# Microcontroller.net
KiCad netlist of a schematic drawn in Altium Designer
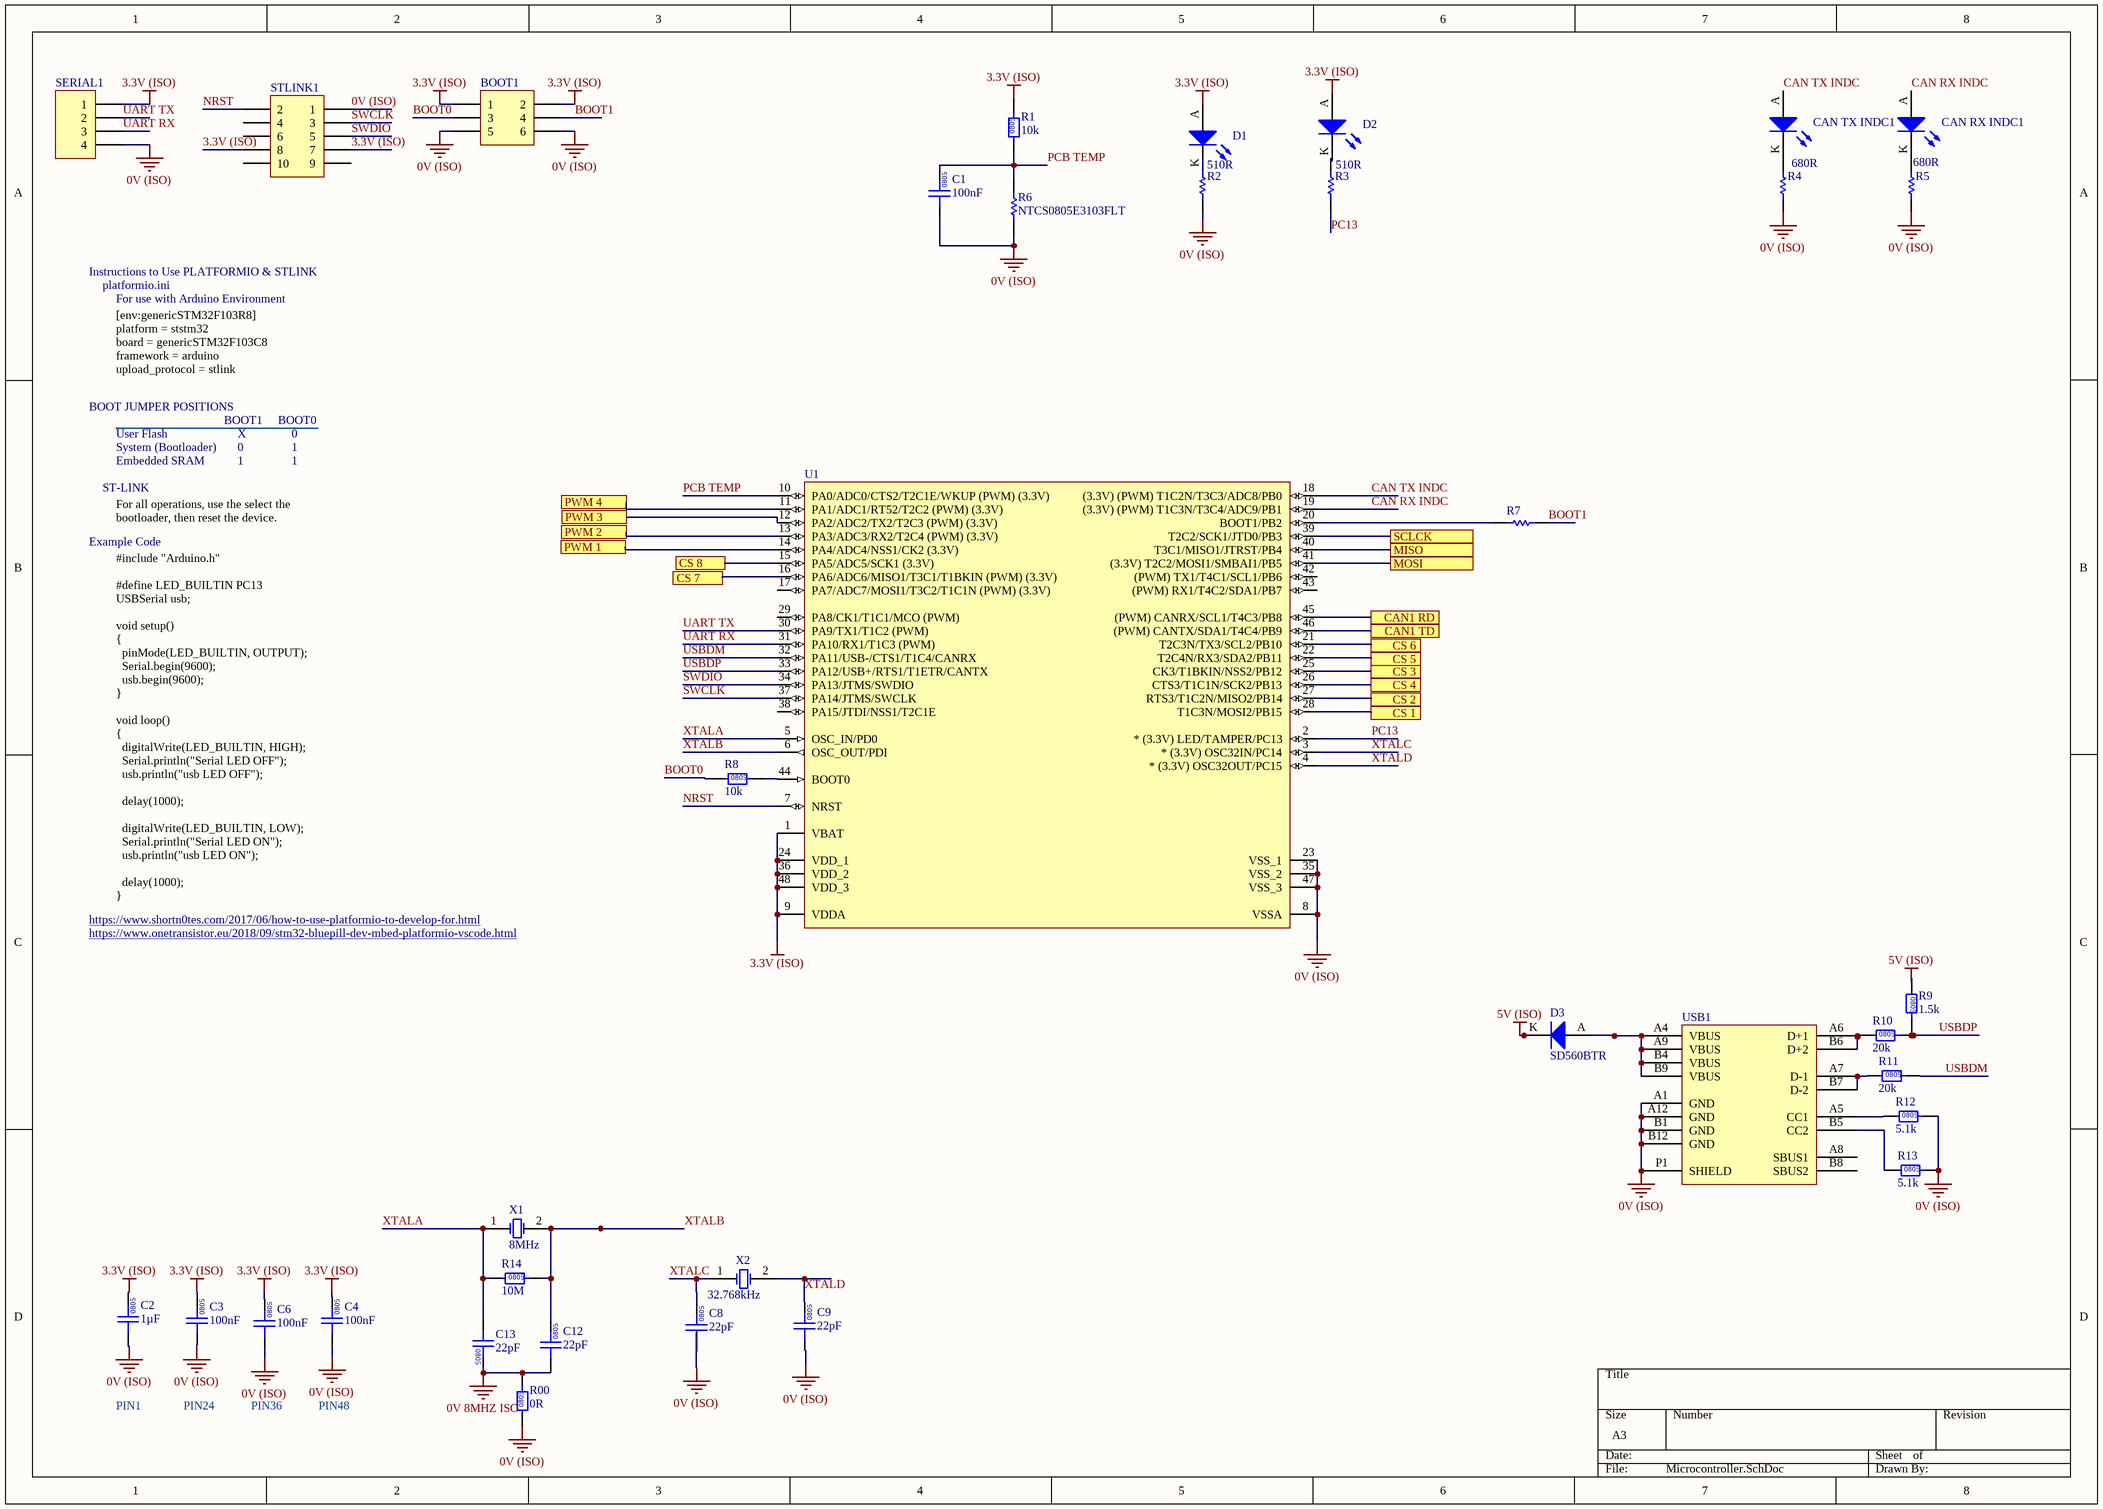
[diagram p0: Microcontroller.SchDoc]

(export (version "E")
  (design (tool "Eeschema 10.0.6"))
  (components
    (comp (ref "BOOT1")
      (value "~")
      (footprint "TH 2.54mm Header 2x3")
      (fields (field (name "PART NUMBER") "TH 2.54mm Header 2x3") (field (name "CONTACT") "NA"))
      (libsource (lib "ts_standard_connectors") (part "Header 2x3"))
    )
    (comp (ref "C1")
      (value "100nF")
      (footprint "0805")
      (fields
        (field (name "PART NUMBER") "GCM21BR71H104KA37L")
        (field (name "MANUFACTURER") "muRata")
        (field (name "TOLERANCE") "±10%")
      )
      (libsource (lib "ts_standard_library") (part "Capacitor 0805"))
    )
    (comp (ref "C2")
      (value "1µF")
      (footprint "0805")
      (fields
        (field (name "PART NUMBER") "GCM21BR71H105KA03L")
        (field (name "MANUFACTURER") "muRata")
        (field (name "TOLERANCE") "±10%")
      )
      (libsource (lib "ts_standard_library") (part "Capacitor 0805"))
    )
    (comp (ref "C3")
      (value "100nF")
      (footprint "0805")
      (fields
        (field (name "PART NUMBER") "GCM21BR71H104KA37L")
        (field (name "MANUFACTURER") "muRata")
        (field (name "TOLERANCE") "±10%")
      )
      (libsource (lib "ts_standard_library") (part "Capacitor 0805"))
    )
    (comp (ref "C4")
      (value "100nF")
      (footprint "0805")
      (fields
        (field (name "PART NUMBER") "GCM21BR71H104KA37L")
        (field (name "MANUFACTURER") "muRata")
        (field (name "TOLERANCE") "±10%")
      )
      (libsource (lib "ts_standard_library") (part "Capacitor 0805"))
    )
    (comp (ref "C6")
      (value "100nF")
      (footprint "0805")
      (fields
        (field (name "PART NUMBER") "GCM21BR71H104KA37L")
        (field (name "MANUFACTURER") "muRata")
        (field (name "TOLERANCE") "±10%")
      )
      (libsource (lib "ts_standard_library") (part "Capacitor 0805"))
    )
    (comp (ref "C8")
      (value "22pF")
      (footprint "0805")
      (fields
        (field (name "PART NUMBER") "GRM21A5C2E220JW01D")
        (field (name "MANUFACTURER") "muRata")
        (field (name "TOLERANCE") "±5%")
      )
      (libsource (lib "ts_standard_library") (part "Capacitor 0805"))
    )
    (comp (ref "C9")
      (value "22pF")
      (footprint "0805")
      (fields
        (field (name "PART NUMBER") "GRM21A5C2E220JW01D")
        (field (name "MANUFACTURER") "muRata")
        (field (name "TOLERANCE") "±5%")
      )
      (libsource (lib "ts_standard_library") (part "Capacitor 0805"))
    )
    (comp (ref "C12")
      (value "22pF")
      (footprint "0805")
      (fields
        (field (name "PART NUMBER") "GRM21A5C2E220JW01D")
        (field (name "MANUFACTURER") "muRata")
        (field (name "TOLERANCE") "±5%")
      )
      (libsource (lib "ts_standard_library") (part "Capacitor 0805"))
    )
    (comp (ref "C13")
      (value "22pF")
      (footprint "0805")
      (fields
        (field (name "PART NUMBER") "GRM21A5C2E220JW01D")
        (field (name "MANUFACTURER") "muRata")
        (field (name "TOLERANCE") "±5%")
      )
      (libsource (lib "ts_standard_library") (part "Capacitor 0805"))
    )
    (comp (ref "CAN RX INDC1")
      (value "~")
      (footprint "0805 LED")
      (description "LED BLUE CLEAR 2012 SMD")
      (fields
        (field (name "PART NUMBER") "SML-MN2BCTT86C")
        (field (name "MANUFACTURER") "ROHM Semiconductor")
      )
      (libsource (lib "ts_standard_library") (part "LED"))
    )
    (comp (ref "CAN TX INDC1")
      (value "~")
      (footprint "0805 LED")
      (description "LED BLUE CLEAR 2012 SMD")
      (fields
        (field (name "PART NUMBER") "SML-MN2BCTT86C")
        (field (name "MANUFACTURER") "ROHM Semiconductor")
      )
      (libsource (lib "ts_standard_library") (part "LED"))
    )
    (comp (ref "D1")
      (value "~")
      (footprint "0805 LED")
      (description "Red LED Indication - Discrete 1.75V 0805 (2012 Metric)")
      (fields (field (name "MANUFACTURER") "ROHM Semiconductor") (field (name "PART NUMBER") "SML-210LTT86"))
      (libsource (lib "ts_standard_library") (part "LED"))
    )
    (comp (ref "D2")
      (value "~")
      (footprint "0805 LED")
      (description "Red LED Indication - Discrete 1.75V 0805 (2012 Metric)")
      (fields (field (name "MANUFACTURER") "ROHM Semiconductor") (field (name "PART NUMBER") "SML-210LTT86"))
      (libsource (lib "ts_standard_library") (part "LED"))
    )
    (comp (ref "D3")
      (value "SD560BTR")
      (footprint "SMB Diode")
      (fields
        (field (name "MANUFACTURER") "SMC Diode Solutions")
        (field (name "DIGIKEY PART NUMBER") "1655-1530-2-ND")
      )
      (libsource (lib "ts_standard_library") (part "Diode"))
    )
    (comp (ref "R00")
      (value "0R")
      (footprint "0805")
      (fields
        (field (name "PART NUMBER") "RC0805FR070RL")
        (field (name "MANUFACTURER") "YAGEO")
        (field (name "TOLERANCE") "0.01")
      )
      (libsource (lib "ts_standard_library") (part "Resistor 0805"))
    )
    (comp (ref "R1")
      (value "10k")
      (footprint "0805")
      (fields
        (field (name "PART NUMBER") "RC0805FR0710KL")
        (field (name "MANUFACTURER") "YAGEO")
        (field (name "TOLERANCE") "0.01")
      )
      (libsource (lib "ts_standard_library") (part "Resistor 0805"))
    )
    (comp (ref "R2")
      (value "510R")
      (footprint "0805")
      (fields
        (field (name "MANUFACTURER") "YAGEO")
        (field (name "PART NUMBER") "RC0805FR07510RL")
        (field (name "TOLERANCE") "0.01")
      )
      (libsource (lib "ts_standard_library") (part "Resistor"))
    )
    (comp (ref "R3")
      (value "510R")
      (footprint "0805")
      (fields
        (field (name "MANUFACTURER") "YAGEO")
        (field (name "PART NUMBER") "RC0805FR07510RL")
        (field (name "TOLERANCE") "0.01")
      )
      (libsource (lib "ts_standard_library") (part "Resistor"))
    )
    (comp (ref "R4")
      (value "680R")
      (footprint "0805")
      (fields
        (field (name "PART NUMBER") "RC0805FR07680RL")
        (field (name "MANUFACTURER") "YAGEO")
        (field (name "TOLERANCE") "0.01")
      )
      (libsource (lib "ts_standard_library") (part "Resistor"))
    )
    (comp (ref "R5")
      (value "680R")
      (footprint "0805")
      (fields
        (field (name "PART NUMBER") "RC0805FR07680RL")
        (field (name "MANUFACTURER") "YAGEO")
        (field (name "TOLERANCE") "0.01")
      )
      (libsource (lib "ts_standard_library") (part "Resistor"))
    )
    (comp (ref "R6")
      (value "NTCS0805E3103FLT")
      (footprint "0805")
      (fields (field (name "TOLERANCE") "0.01") (field (name "DIGIKEY PART NUMBER") "BC2733CT-ND"))
      (libsource (lib "Team Swinburne") (part "Resistor"))
    )
    (comp (ref "R7")
      (value "~")
      (footprint "0805")
      (fields
        (field (name "PART NUMBER") "RC0805FR0710KL")
        (field (name "MANUFACTURER") "YAGEO")
        (field (name "TOLERANCE") "0.01")
      )
      (libsource (lib "ts_standard_library") (part "Resistor"))
    )
    (comp (ref "R8")
      (value "10k")
      (footprint "0805")
      (fields
        (field (name "PART NUMBER") "RC0805FR0710KL")
        (field (name "MANUFACTURER") "YAGEO")
        (field (name "TOLERANCE") "0.01")
      )
      (libsource (lib "ts_standard_library") (part "Resistor 0805"))
    )
    (comp (ref "R9")
      (value "1.5k")
      (footprint "0805")
      (fields
        (field (name "PART NUMBER") "RC0805FR071K5L")
        (field (name "MANUFACTURER") "YAGEO")
        (field (name "TOLERANCE") "0.01")
      )
      (libsource (lib "ts_standard_library") (part "Resistor 0805"))
    )
    (comp (ref "R10")
      (value "20k")
      (footprint "0805")
      (fields
        (field (name "PART NUMBER") "RC0805FR0720KL")
        (field (name "MANUFACTURER") "YAGEO")
        (field (name "TOLERANCE") "0.01")
      )
      (libsource (lib "ts_standard_library") (part "Resistor 0805"))
    )
    (comp (ref "R11")
      (value "20k")
      (footprint "0805")
      (fields
        (field (name "PART NUMBER") "RC0805FR0720KL")
        (field (name "MANUFACTURER") "YAGEO")
        (field (name "TOLERANCE") "0.01")
      )
      (libsource (lib "ts_standard_library") (part "Resistor 0805"))
    )
    (comp (ref "R12")
      (value "5.1k")
      (footprint "0805")
      (fields
        (field (name "PART NUMBER") "RC0805FR075K1L")
        (field (name "MANUFACTURER") "YAGEO")
        (field (name "TOLERANCE") "0.01")
      )
      (libsource (lib "ts_standard_library") (part "Resistor 0805"))
    )
    (comp (ref "R13")
      (value "5.1k")
      (footprint "0805")
      (fields
        (field (name "PART NUMBER") "RC0805FR075K1L")
        (field (name "MANUFACTURER") "YAGEO")
        (field (name "TOLERANCE") "0.01")
      )
      (libsource (lib "ts_standard_library") (part "Resistor 0805"))
    )
    (comp (ref "R14")
      (value "10M")
      (footprint "0805")
      (fields
        (field (name "PART NUMBER") "RC0805FR0710ML")
        (field (name "MANUFACTURER") "YAGEO")
        (field (name "TOLERANCE") "0.01")
      )
      (libsource (lib "ts_standard_library") (part "Resistor 0805"))
    )
    (comp (ref "SERIAL1")
      (value "~")
      (footprint "TH 2.54mm Header 1x4")
      (fields (field (name "PART NUMBER") "TH 2.54mm Header 1x4") (field (name "CONTACT") "NA"))
      (libsource (lib "ts_standard_connectors") (part "Header 1x4"))
    )
    (comp (ref "STLINK1")
      (value "~")
      (footprint "TH 2.54mm Header 2x5")
      (fields (field (name "PART NUMBER") "TH 2.54mm Header 2x5") (field (name "CONTACT") "NA"))
      (libsource (lib "ts_standard_connectors") (part "Header 2x5"))
    )
    (comp (ref "U1")
      (value "~")
      (footprint "STM 48-LQFP")
      (description "ARM® Cortex®-M3 STM32F1 Microcontroller IC 32-Bit 72MHz 64KB (64K x 8) FLASH")
      (fields (field (name "PART NUMBER") "STM32F103C8T6") (field (name "MANUFACTURER") "STMicroelectronics"))
      (libsource (lib "ts_standard_library") (part "STM32F103C8T6"))
    )
    (comp (ref "USB1")
      (value "~")
      (footprint "USB4085-GF-A")
      (description "USB - C (Type - C) USB 2.0 Receptacle Connector 16 Position Through Hole, Right Angle")
      (fields
        (field (name "PART NUMBER") "USB4085-GF-A")
        (field (name "DIGIKEY PART NUMBER") "2073-USB4085-GF-ACT-ND")
      )
      (libsource (lib "ts_standard_connectors") (part "USB4085-GF-A"))
    )
    (comp (ref "X1")
      (value "8MHz")
      (footprint "Abracon HC-49/US")
      (fields
        (field (name "PART NUMBER") "ABLS-8.000MHZ-B4-T")
        (field (name "MANUFACTURER") "Abracon LLC")
        (field (name "DIGIKEY PART NUMBER") "535-10212-2-ND")
      )
      (libsource (lib "ts_standard_library") (part "Crystal"))
    )
    (comp (ref "X2")
      (value "32.768kHz")
      (footprint "EPSON 2-SMD")
      (fields
        (field (name "PART NUMBER") "FC-135 32.7680KA-A5")
        (field (name "MANUFACTURER") "EPSON")
        (field (name "DIGIKEY PART NUMBER") "SER4103TR-ND")
      )
      (libsource (lib "ts_standard_library") (part "Crystal"))
    )
  )
  (nets
    (net (code "1") (name "/BOOT0") (class "Default")
      (node (ref "BOOT1") (pin "3") (pinfunction "3_3") (pintype "passive"))
      (node (ref "R8") (pin "1") (pinfunction "1_1") (pintype "passive"))
    )
    (net (code "2") (name "/BOOT1") (class "Default")
      (node (ref "BOOT1") (pin "4") (pinfunction "4_4") (pintype "passive"))
      (node (ref "R7") (pin "2") (pinfunction "2_2") (pintype "passive"))
    )
    (net (code "3") (name "/CAN RX INDC") (class "Default")
      (node (ref "CAN RX INDC1") (pin "A") (pinfunction "A_A") (pintype "passive"))
      (node (ref "U1") (pin "19") (pinfunction "(3.3V)_(PWM)_T1C3N/T3C4/ADC9/PB1_19") (pintype "bidirectional"))
    )
    (net (code "4") (name "/CAN TX INDC") (class "Default")
      (node (ref "CAN TX INDC1") (pin "A") (pinfunction "A_A") (pintype "passive"))
      (node (ref "U1") (pin "18") (pinfunction "(3.3V)_(PWM)_T1C2N/T3C3/ADC8/PB0_18") (pintype "bidirectional"))
    )
    (net (code "5") (name "/CAN1 RD") (class "Default")
      (node (ref "U1") (pin "45") (pinfunction "(PWM)_CANRX/SCL1/T4C3/PB8_45") (pintype "bidirectional"))
    )
    (net (code "6") (name "/CAN1 TD") (class "Default")
      (node (ref "U1") (pin "46") (pinfunction "(PWM)_CANTX/SDA1/T4C4/PB9_46") (pintype "bidirectional"))
    )
    (net (code "7") (name "/CS 1") (class "Default")
      (node (ref "U1") (pin "28") (pinfunction "T1C3N/MOSI2/PB15_28") (pintype "bidirectional"))
    )
    (net (code "8") (name "/CS 2") (class "Default")
      (node (ref "U1") (pin "27") (pinfunction "RTS3/T1C2N/MISO2/PB14_27") (pintype "bidirectional"))
    )
    (net (code "9") (name "/CS 3") (class "Default")
      (node (ref "U1") (pin "25") (pinfunction "CK3/T1BKIN/NSS2/PB12_25") (pintype "bidirectional"))
    )
    (net (code "10") (name "/CS 4") (class "Default")
      (node (ref "U1") (pin "26") (pinfunction "CTS3/T1C1N/SCK2/PB13_26") (pintype "bidirectional"))
    )
    (net (code "11") (name "/CS 5") (class "Default")
      (node (ref "U1") (pin "22") (pinfunction "T2C4N/RX3/SDA2/PB11_22") (pintype "bidirectional"))
    )
    (net (code "12") (name "/CS 6") (class "Default")
      (node (ref "U1") (pin "21") (pinfunction "T2C3N/TX3/SCL2/PB10_21") (pintype "bidirectional"))
    )
    (net (code "13") (name "/CS 7") (class "Default")
      (node (ref "U1") (pin "16") (pinfunction "PA6/ADC6/MISO1/T3C1/T1BKIN_(PWM)_(3.3V)_16") (pintype "bidirectional"))
    )
    (net (code "14") (name "/CS 8") (class "Default")
      (node (ref "U1") (pin "15") (pinfunction "PA5/ADC5/SCK1_(3.3V)_15") (pintype "bidirectional"))
    )
    (net (code "15") (name "/MISO") (class "Default")
      (node (ref "U1") (pin "40") (pinfunction "T3C1/MISO1/JTRST/PB4_40") (pintype "bidirectional"))
    )
    (net (code "16") (name "/MOSI") (class "Default")
      (node (ref "U1") (pin "41") (pinfunction "(3.3V)_T2C2/MOSI1/SMBAI1/PB5_41") (pintype "bidirectional"))
    )
    (net (code "17") (name "/NRST") (class "Default")
      (node (ref "STLINK1") (pin "2") (pinfunction "2_2") (pintype "passive"))
      (node (ref "U1") (pin "7") (pinfunction "NRST_7") (pintype "bidirectional"))
    )
    (net (code "18") (name "/PC13") (class "Default")
      (node (ref "R3") (pin "1") (pinfunction "1_1") (pintype "passive"))
      (node (ref "U1") (pin "2") (pinfunction "*_(3.3V)_LED/TAMPER/PC13_2") (pintype "bidirectional"))
    )
    (net (code "19") (name "/PCB TEMP") (class "Default")
      (node (ref "C1") (pin "2") (pinfunction "2_2") (pintype "passive"))
      (node (ref "R1") (pin "1") (pinfunction "1_1") (pintype "passive"))
      (node (ref "R6") (pin "2") (pinfunction "2_2") (pintype "passive"))
      (node (ref "U1") (pin "10") (pinfunction "PA0/ADC0/CTS2/T2C1E/WKUP_(PWM)_(3.3V)_10") (pintype "bidirectional"))
    )
    (net (code "20") (name "/PWM 1") (class "Default")
      (node (ref "U1") (pin "14") (pinfunction "PA4/ADC4/NSS1/CK2_(3.3V)_14") (pintype "bidirectional"))
    )
    (net (code "21") (name "/PWM 2") (class "Default")
      (node (ref "U1") (pin "13") (pinfunction "PA3/ADC3/RX2/T2C4_(PWM)_(3.3V)_13") (pintype "bidirectional"))
    )
    (net (code "22") (name "/PWM 3") (class "Default")
      (node (ref "U1") (pin "12") (pinfunction "PA2/ADC2/TX2/T2C3_(PWM)_(3.3V)_12") (pintype "bidirectional"))
    )
    (net (code "23") (name "/PWM 4") (class "Default")
      (node (ref "U1") (pin "11") (pinfunction "PA1/ADC1/RT52/T2C2_(PWM)_(3.3V)_11") (pintype "bidirectional"))
    )
    (net (code "24") (name "/SCLCK") (class "Default")
      (node (ref "U1") (pin "39") (pinfunction "T2C2/SCK1/JTD0/PB3_39") (pintype "bidirectional"))
    )
    (net (code "25") (name "/SWCLK") (class "Default")
      (node (ref "STLINK1") (pin "3") (pinfunction "3_3") (pintype "passive"))
      (node (ref "U1") (pin "37") (pinfunction "PA14/JTMS/SWCLK_37") (pintype "bidirectional"))
    )
    (net (code "26") (name "/SWDIO") (class "Default")
      (node (ref "STLINK1") (pin "5") (pinfunction "5_5") (pintype "passive"))
      (node (ref "U1") (pin "34") (pinfunction "PA13/JTMS/SWDIO_34") (pintype "bidirectional"))
    )
    (net (code "27") (name "/UART RX") (class "Default")
      (node (ref "SERIAL1") (pin "3") (pinfunction "3_3") (pintype "passive"))
      (node (ref "U1") (pin "31") (pinfunction "PA10/RX1/T1C3_(PWM)_31") (pintype "bidirectional"))
    )
    (net (code "28") (name "/UART TX") (class "Default")
      (node (ref "SERIAL1") (pin "2") (pinfunction "2_2") (pintype "passive"))
      (node (ref "U1") (pin "30") (pinfunction "PA9/TX1/T1C2_(PWM)_30") (pintype "bidirectional"))
    )
    (net (code "29") (name "/USBDM") (class "Default")
      (node (ref "R11") (pin "2") (pinfunction "2_2") (pintype "passive"))
      (node (ref "U1") (pin "32") (pinfunction "PA11/USB-/CTS1/T1C4/CANRX_32") (pintype "bidirectional"))
    )
    (net (code "30") (name "/USBDP") (class "Default")
      (node (ref "R10") (pin "2") (pinfunction "2_2") (pintype "passive"))
      (node (ref "R9") (pin "2") (pinfunction "2_2") (pintype "passive"))
      (node (ref "U1") (pin "33") (pinfunction "PA12/USB+/RTS1/T1ETR/CANTX_33") (pintype "bidirectional"))
    )
    (net (code "31") (name "/XTALA") (class "Default")
      (node (ref "C13") (pin "1") (pinfunction "1_1") (pintype "passive"))
      (node (ref "R14") (pin "1") (pinfunction "1_1") (pintype "passive"))
      (node (ref "U1") (pin "5") (pinfunction "OSC_IN/PD0_5") (pintype "input"))
      (node (ref "X1") (pin "1") (pinfunction "OSC1_1") (pintype "passive"))
    )
    (net (code "32") (name "/XTALB") (class "Default")
      (node (ref "C12") (pin "2") (pinfunction "2_2") (pintype "passive"))
      (node (ref "R14") (pin "2") (pinfunction "2_2") (pintype "passive"))
      (node (ref "U1") (pin "6") (pinfunction "OSC_OUT/PDI_6") (pintype "output"))
      (node (ref "X1") (pin "2") (pinfunction "OSC2_2") (pintype "passive"))
    )
    (net (code "33") (name "/XTALC") (class "Default")
      (node (ref "C8") (pin "2") (pinfunction "2_2") (pintype "passive"))
      (node (ref "U1") (pin "3") (pinfunction "*_(3.3V)_OSC32IN/PC14_3") (pintype "bidirectional"))
      (node (ref "X2") (pin "1") (pinfunction "OSC1_1") (pintype "passive"))
    )
    (net (code "34") (name "/XTALD") (class "Default")
      (node (ref "C9") (pin "2") (pinfunction "2_2") (pintype "passive"))
      (node (ref "U1") (pin "4") (pinfunction "*_(3.3V)_OSC32OUT/PC15_4") (pintype "bidirectional"))
      (node (ref "X2") (pin "2") (pinfunction "OSC2_2") (pintype "passive"))
    )
    (net (code "35") (name "0V (ISO)") (class "Default")
      (node (ref "BOOT1") (pin "5") (pinfunction "5_5") (pintype "passive"))
      (node (ref "BOOT1") (pin "6") (pinfunction "6_6") (pintype "passive"))
      (node (ref "C1") (pin "1") (pinfunction "1_1") (pintype "passive"))
      (node (ref "C2") (pin "1") (pinfunction "1_1") (pintype "passive"))
      (node (ref "C3") (pin "1") (pinfunction "1_1") (pintype "passive"))
      (node (ref "C4") (pin "1") (pinfunction "1_1") (pintype "passive"))
      (node (ref "C6") (pin "1") (pinfunction "1_1") (pintype "passive"))
      (node (ref "C8") (pin "1") (pinfunction "1_1") (pintype "passive"))
      (node (ref "C9") (pin "1") (pinfunction "1_1") (pintype "passive"))
      (node (ref "R00") (pin "1") (pinfunction "1_1") (pintype "passive"))
      (node (ref "R12") (pin "2") (pinfunction "2_2") (pintype "passive"))
      (node (ref "R13") (pin "2") (pinfunction "2_2") (pintype "passive"))
      (node (ref "R2") (pin "1") (pinfunction "1_1") (pintype "passive"))
      (node (ref "R4") (pin "1") (pinfunction "1_1") (pintype "passive"))
      (node (ref "R5") (pin "1") (pinfunction "1_1") (pintype "passive"))
      (node (ref "R6") (pin "1") (pinfunction "1_1") (pintype "passive"))
      (node (ref "SERIAL1") (pin "4") (pinfunction "4_4") (pintype "passive"))
      (node (ref "STLINK1") (pin "1") (pinfunction "1_1") (pintype "passive"))
      (node (ref "U1") (pin "23") (pinfunction "VSS_1_23") (pintype "power_in"))
      (node (ref "U1") (pin "35") (pinfunction "VSS_2_35") (pintype "power_in"))
      (node (ref "U1") (pin "47") (pinfunction "VSS_3_47") (pintype "power_in"))
      (node (ref "U1") (pin "8") (pinfunction "VSSA_8") (pintype "power_in"))
      (node (ref "USB1") (pin "A1") (pinfunction "GND_A1") (pintype "passive"))
      (node (ref "USB1") (pin "A12") (pinfunction "GND_A12") (pintype "passive"))
      (node (ref "USB1") (pin "B1") (pinfunction "GND_B1") (pintype "passive"))
      (node (ref "USB1") (pin "B12") (pinfunction "GND_B12") (pintype "passive"))
      (node (ref "USB1") (pin "P1") (pinfunction "SHIELD_P1") (pintype "passive"))
    )
    (net (code "36") (name "0V 8MHZ ISO") (class "Default")
      (node (ref "C12") (pin "1") (pinfunction "1_1") (pintype "passive"))
      (node (ref "C13") (pin "2") (pinfunction "2_2") (pintype "passive"))
      (node (ref "R00") (pin "2") (pinfunction "2_2") (pintype "passive"))
    )
    (net (code "37") (name "3.3V (ISO)") (class "Default")
      (node (ref "BOOT1") (pin "1") (pinfunction "1_1") (pintype "passive"))
      (node (ref "BOOT1") (pin "2") (pinfunction "2_2") (pintype "passive"))
      (node (ref "C2") (pin "2") (pinfunction "2_2") (pintype "passive"))
      (node (ref "C3") (pin "2") (pinfunction "2_2") (pintype "passive"))
      (node (ref "C4") (pin "2") (pinfunction "2_2") (pintype "passive"))
      (node (ref "C6") (pin "2") (pinfunction "2_2") (pintype "passive"))
      (node (ref "D1") (pin "A") (pinfunction "A_A") (pintype "passive"))
      (node (ref "D2") (pin "A") (pinfunction "A_A") (pintype "passive"))
      (node (ref "R1") (pin "2") (pinfunction "2_2") (pintype "passive"))
      (node (ref "SERIAL1") (pin "1") (pinfunction "1_1") (pintype "passive"))
      (node (ref "STLINK1") (pin "7") (pinfunction "7_7") (pintype "passive"))
      (node (ref "STLINK1") (pin "8") (pinfunction "8_8") (pintype "passive"))
      (node (ref "U1") (pin "1") (pinfunction "VBAT_1") (pintype "power_in"))
      (node (ref "U1") (pin "24") (pinfunction "VDD_1_24") (pintype "power_in"))
      (node (ref "U1") (pin "36") (pinfunction "VDD_2_36") (pintype "power_in"))
      (node (ref "U1") (pin "48") (pinfunction "VDD_3_48") (pintype "power_in"))
      (node (ref "U1") (pin "9") (pinfunction "VDDA_9") (pintype "power_in"))
    )
    (net (code "38") (name "5V (ISO)") (class "Default")
      (node (ref "D3") (pin "K") (pinfunction "K_K") (pintype "passive"))
      (node (ref "R9") (pin "1") (pinfunction "1_1") (pintype "passive"))
    )
    (net (code "39") (name "Net-(CAN RX INDC1-PadK)") (class "Default")
      (node (ref "CAN RX INDC1") (pin "K") (pinfunction "K_K") (pintype "passive"))
      (node (ref "R5") (pin "2") (pinfunction "2_2") (pintype "passive"))
    )
    (net (code "40") (name "Net-(CAN TX INDC1-PadK)") (class "Default")
      (node (ref "CAN TX INDC1") (pin "K") (pinfunction "K_K") (pintype "passive"))
      (node (ref "R4") (pin "2") (pinfunction "2_2") (pintype "passive"))
    )
    (net (code "41") (name "Net-(D1-PadK)") (class "Default")
      (node (ref "D1") (pin "K") (pinfunction "K_K") (pintype "passive"))
      (node (ref "R2") (pin "2") (pinfunction "2_2") (pintype "passive"))
    )
    (net (code "42") (name "Net-(D2-PadK)") (class "Default")
      (node (ref "D2") (pin "K") (pinfunction "K_K") (pintype "passive"))
      (node (ref "R3") (pin "2") (pinfunction "2_2") (pintype "passive"))
    )
    (net (code "43") (name "Net-(D3-PadA)") (class "Default")
      (node (ref "D3") (pin "A") (pinfunction "A_A") (pintype "passive"))
      (node (ref "USB1") (pin "A4") (pinfunction "VBUS_A4") (pintype "passive"))
      (node (ref "USB1") (pin "A9") (pinfunction "VBUS_A9") (pintype "passive"))
      (node (ref "USB1") (pin "B4") (pinfunction "VBUS_B4") (pintype "passive"))
      (node (ref "USB1") (pin "B9") (pinfunction "VBUS_B9") (pintype "passive"))
    )
    (net (code "44") (name "Net-(U1-BOOT0)") (class "Default")
      (node (ref "R8") (pin "2") (pinfunction "2_2") (pintype "passive"))
      (node (ref "U1") (pin "44") (pinfunction "BOOT0_44") (pintype "input"))
    )
    (net (code "45") (name "Net-(U1-BOOT1{slash}PB2)") (class "Default")
      (node (ref "R7") (pin "1") (pinfunction "1_1") (pintype "passive"))
      (node (ref "U1") (pin "20") (pinfunction "BOOT1/PB2_20") (pintype "bidirectional"))
    )
    (net (code "46") (name "Net-(USB1-CC1)") (class "Default")
      (node (ref "R12") (pin "1") (pinfunction "1_1") (pintype "passive"))
      (node (ref "USB1") (pin "A5") (pinfunction "CC1_A5") (pintype "passive"))
    )
    (net (code "47") (name "Net-(USB1-CC2)") (class "Default")
      (node (ref "R13") (pin "1") (pinfunction "1_1") (pintype "passive"))
      (node (ref "USB1") (pin "B5") (pinfunction "CC2_B5") (pintype "passive"))
    )
    (net (code "48") (name "Net-(USB1-D+1)") (class "Default")
      (node (ref "R10") (pin "1") (pinfunction "1_1") (pintype "passive"))
      (node (ref "USB1") (pin "A6") (pinfunction "D+1_A6") (pintype "passive"))
      (node (ref "USB1") (pin "B6") (pinfunction "D+2_B6") (pintype "passive"))
    )
    (net (code "49") (name "Net-(USB1-D-1)") (class "Default")
      (node (ref "R11") (pin "1") (pinfunction "1_1") (pintype "passive"))
      (node (ref "USB1") (pin "A7") (pinfunction "D-1_A7") (pintype "passive"))
      (node (ref "USB1") (pin "B7") (pinfunction "D-2_B7") (pintype "passive"))
    )
    (net (code "50") (name "unconnected-(STLINK1-Pad4)") (class "Default")
      (node (ref "STLINK1") (pin "4") (pinfunction "4_4") (pintype "passive"))
    )
    (net (code "51") (name "unconnected-(STLINK1-Pad6)") (class "Default")
      (node (ref "STLINK1") (pin "6") (pinfunction "6_6") (pintype "passive"))
    )
    (net (code "52") (name "unconnected-(STLINK1-Pad9)") (class "Default")
      (node (ref "STLINK1") (pin "9") (pinfunction "9_9") (pintype "passive"))
    )
    (net (code "53") (name "unconnected-(STLINK1-Pad10)") (class "Default")
      (node (ref "STLINK1") (pin "10") (pinfunction "10_10") (pintype "passive"))
    )
    (net (code "54") (name "unconnected-(U1-(PWM)_RX1{slash}T4C2{slash}SDA1{slash}PB7-Pad43)") (class "Default")
      (node (ref "U1") (pin "43") (pinfunction "(PWM)_RX1/T4C2/SDA1/PB7_43") (pintype "bidirectional"))
    )
    (net (code "55") (name "unconnected-(U1-(PWM)_TX1{slash}T4C1{slash}SCL1{slash}PB6-Pad42)") (class "Default")
      (node (ref "U1") (pin "42") (pinfunction "(PWM)_TX1/T4C1/SCL1/PB6_42") (pintype "bidirectional"))
    )
    (net (code "56") (name "unconnected-(U1-PA7{slash}ADC7{slash}MOSI1{slash}T3C2{slash}T1C1N_(PWM)_(3.3V)-Pad17)") (class "Default")
      (node (ref "U1") (pin "17") (pinfunction "PA7/ADC7/MOSI1/T3C2/T1C1N_(PWM)_(3.3V)_17") (pintype "bidirectional"))
    )
    (net (code "57") (name "unconnected-(U1-PA8{slash}CK1{slash}T1C1{slash}MCO_(PWM)-Pad29)") (class "Default")
      (node (ref "U1") (pin "29") (pinfunction "PA8/CK1/T1C1/MCO_(PWM)_29") (pintype "bidirectional"))
    )
    (net (code "58") (name "unconnected-(U1-PA15{slash}JTDI{slash}NSS1{slash}T2C1E-Pad38)") (class "Default")
      (node (ref "U1") (pin "38") (pinfunction "PA15/JTDI/NSS1/T2C1E_38") (pintype "bidirectional"))
    )
    (net (code "59") (name "unconnected-(USB1-SBUS1-PadA8)") (class "Default")
      (node (ref "USB1") (pin "A8") (pinfunction "SBUS1_A8") (pintype "passive"))
    )
    (net (code "60") (name "unconnected-(USB1-SBUS2-PadB8)") (class "Default")
      (node (ref "USB1") (pin "B8") (pinfunction "SBUS2_B8") (pintype "passive"))
    )
  )
)
